# xt60_pcb.net
KiCad netlist of a schematic drawn in EAGLE
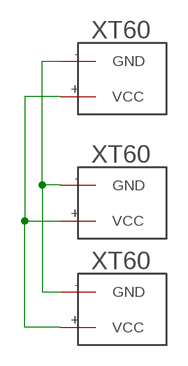
[diagram p0: schematic, sheet 1]

(export (version "E")
  (design (tool "Eeschema 10.0.6"))
  (components
    (comp (ref "U$1")
      (value "XT60")
      (footprint "eagle-import:XT60")
      (libsource (lib "eagle-import") (part "XT60"))
    )
    (comp (ref "U$2")
      (value "XT60")
      (footprint "eagle-import:XT60")
      (libsource (lib "eagle-import") (part "XT60"))
    )
    (comp (ref "U$3")
      (value "XT60")
      (footprint "eagle-import:XT60")
      (libsource (lib "eagle-import") (part "XT60"))
    )
  )
  (nets
    (net (code "1") (name "Net-(U$1-GND)") (class "Default")
      (node (ref "U$1") (pin "-") (pinfunction "GND_-") (pintype "bidirectional"))
      (node (ref "U$2") (pin "-") (pinfunction "GND_-") (pintype "bidirectional"))
      (node (ref "U$3") (pin "-") (pinfunction "GND_-") (pintype "bidirectional"))
    )
    (net (code "2") (name "Net-(U$1-VCC)") (class "Default")
      (node (ref "U$1") (pin "+") (pinfunction "VCC_+") (pintype "bidirectional"))
      (node (ref "U$2") (pin "+") (pinfunction "VCC_+") (pintype "bidirectional"))
      (node (ref "U$3") (pin "+") (pinfunction "VCC_+") (pintype "bidirectional"))
    )
  )
)
